# STM32F4_TFT-Proto_Adapter.net
KiCad netlist of a schematic drawn in EAGLE
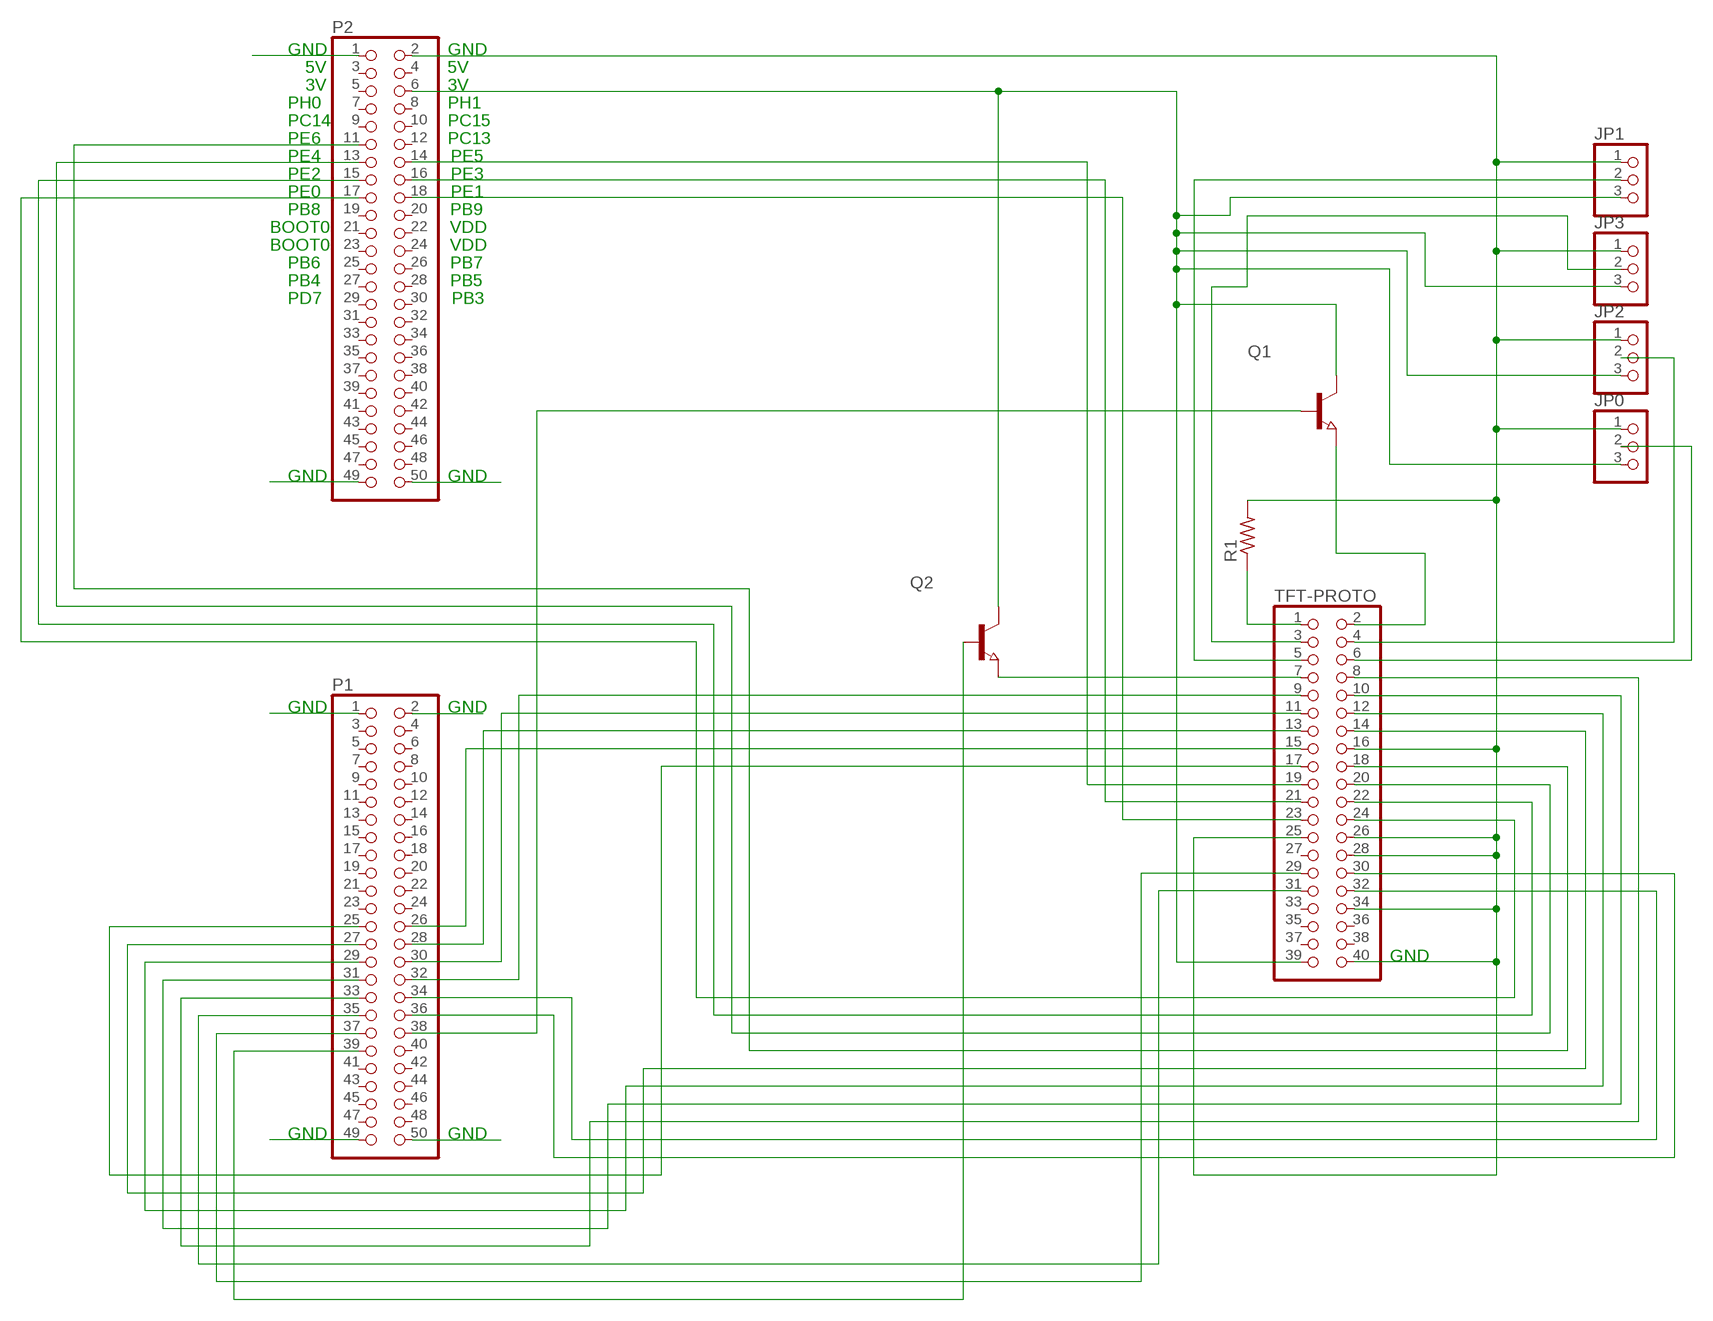
[diagram p0: schematic, sheet 1]

(export (version "E")
  (design (tool "Eeschema 10.0.6"))
  (components
    (comp (ref "JP0")
      (value "PINHD-1X3")
      (footprint "eagle-import:1X03")
      (libsource (lib "eagle-import") (part "PINHD-1X3"))
    )
    (comp (ref "JP1")
      (value "PINHD-1X3")
      (footprint "eagle-import:1X03")
      (libsource (lib "eagle-import") (part "PINHD-1X3"))
    )
    (comp (ref "JP2")
      (value "PINHD-1X3")
      (footprint "eagle-import:1X03")
      (libsource (lib "eagle-import") (part "PINHD-1X3"))
    )
    (comp (ref "JP3")
      (value "PINHD-1X3")
      (footprint "eagle-import:1X03")
      (libsource (lib "eagle-import") (part "PINHD-1X3"))
    )
    (comp (ref "P1")
      (value "PINHD-2X25")
      (footprint "eagle-import:2X25")
      (libsource (lib "eagle-import") (part "PINHD-2X25"))
    )
    (comp (ref "P2")
      (value "PINHD-2X25")
      (footprint "eagle-import:2X25")
      (libsource (lib "eagle-import") (part "PINHD-2X25"))
    )
    (comp (ref "Q1")
      (value "NPN-TRANSISTOR_SOT23")
      (footprint "eagle-import:SOT23")
      (libsource (lib "eagle-import") (part "NPN-TRANSISTOR_SOT23"))
    )
    (comp (ref "Q2")
      (value "NPN-TRANSISTOR_SOT23")
      (footprint "eagle-import:SOT23")
      (libsource (lib "eagle-import") (part "NPN-TRANSISTOR_SOT23"))
    )
    (comp (ref "R1")
      (value "R-US_R0805")
      (footprint "eagle-import:R0805")
      (libsource (lib "eagle-import") (part "R-US_R0805"))
    )
    (comp (ref "TFT-PROTO")
      (value "PINHD-2X20")
      (footprint "eagle-import:2X20")
      (libsource (lib "eagle-import") (part "PINHD-2X20"))
    )
  )
  (nets
    (net (code "1") (name "/GND") (class "Default")
      (node (ref "JP0") (pin "1") (pinfunction "1_1") (pintype "passive"))
      (node (ref "JP1") (pin "1") (pinfunction "1_1") (pintype "passive"))
      (node (ref "JP2") (pin "1") (pinfunction "1_1") (pintype "passive"))
      (node (ref "JP3") (pin "1") (pinfunction "1_1") (pintype "passive"))
      (node (ref "P1") (pin "1") (pinfunction "1_1") (pintype "passive"))
      (node (ref "P1") (pin "2") (pinfunction "2_2") (pintype "passive"))
      (node (ref "P1") (pin "49") (pinfunction "49_49") (pintype "passive"))
      (node (ref "P1") (pin "50") (pinfunction "50_50") (pintype "passive"))
      (node (ref "P2") (pin "1") (pinfunction "1_1") (pintype "passive"))
      (node (ref "P2") (pin "2") (pinfunction "2_2") (pintype "passive"))
      (node (ref "P2") (pin "49") (pinfunction "49_49") (pintype "passive"))
      (node (ref "P2") (pin "50") (pinfunction "50_50") (pintype "passive"))
      (node (ref "R1") (pin "2") (pinfunction "2_2") (pintype "passive"))
      (node (ref "TFT-PROTO") (pin "16") (pinfunction "16_16") (pintype "passive"))
      (node (ref "TFT-PROTO") (pin "25") (pinfunction "25_25") (pintype "passive"))
      (node (ref "TFT-PROTO") (pin "26") (pinfunction "26_26") (pintype "passive"))
      (node (ref "TFT-PROTO") (pin "28") (pinfunction "28_28") (pintype "passive"))
      (node (ref "TFT-PROTO") (pin "34") (pinfunction "34_34") (pintype "passive"))
      (node (ref "TFT-PROTO") (pin "40") (pinfunction "40_40") (pintype "passive"))
    )
    (net (code "2") (name "Net-(JP0-Pad2)") (class "Default")
      (node (ref "JP0") (pin "2") (pinfunction "2_2") (pintype "passive"))
      (node (ref "TFT-PROTO") (pin "6") (pinfunction "6_6") (pintype "passive"))
    )
    (net (code "3") (name "Net-(JP1-Pad2)") (class "Default")
      (node (ref "JP1") (pin "2") (pinfunction "2_2") (pintype "passive"))
      (node (ref "TFT-PROTO") (pin "5") (pinfunction "5_5") (pintype "passive"))
    )
    (net (code "4") (name "Net-(JP2-Pad2)") (class "Default")
      (node (ref "JP2") (pin "2") (pinfunction "2_2") (pintype "passive"))
      (node (ref "TFT-PROTO") (pin "4") (pinfunction "4_4") (pintype "passive"))
    )
    (net (code "5") (name "Net-(JP3-Pad2)") (class "Default")
      (node (ref "JP3") (pin "2") (pinfunction "2_2") (pintype "passive"))
      (node (ref "TFT-PROTO") (pin "3") (pinfunction "3_3") (pintype "passive"))
    )
    (net (code "6") (name "Net-(P1-Pad25)") (class "Default")
      (node (ref "P1") (pin "25") (pinfunction "25_25") (pintype "passive"))
      (node (ref "TFT-PROTO") (pin "17") (pinfunction "17_17") (pintype "passive"))
    )
    (net (code "7") (name "Net-(P1-Pad26)") (class "Default")
      (node (ref "P1") (pin "26") (pinfunction "26_26") (pintype "passive"))
      (node (ref "TFT-PROTO") (pin "15") (pinfunction "15_15") (pintype "passive"))
    )
    (net (code "8") (name "Net-(P1-Pad27)") (class "Default")
      (node (ref "P1") (pin "27") (pinfunction "27_27") (pintype "passive"))
      (node (ref "TFT-PROTO") (pin "14") (pinfunction "14_14") (pintype "passive"))
    )
    (net (code "9") (name "Net-(P1-Pad28)") (class "Default")
      (node (ref "P1") (pin "28") (pinfunction "28_28") (pintype "passive"))
      (node (ref "TFT-PROTO") (pin "13") (pinfunction "13_13") (pintype "passive"))
    )
    (net (code "10") (name "Net-(P1-Pad29)") (class "Default")
      (node (ref "P1") (pin "29") (pinfunction "29_29") (pintype "passive"))
      (node (ref "TFT-PROTO") (pin "12") (pinfunction "12_12") (pintype "passive"))
    )
    (net (code "11") (name "Net-(P1-Pad30)") (class "Default")
      (node (ref "P1") (pin "30") (pinfunction "30_30") (pintype "passive"))
      (node (ref "TFT-PROTO") (pin "11") (pinfunction "11_11") (pintype "passive"))
    )
    (net (code "12") (name "Net-(P1-Pad31)") (class "Default")
      (node (ref "P1") (pin "31") (pinfunction "31_31") (pintype "passive"))
      (node (ref "TFT-PROTO") (pin "10") (pinfunction "10_10") (pintype "passive"))
    )
    (net (code "13") (name "Net-(P1-Pad32)") (class "Default")
      (node (ref "P1") (pin "32") (pinfunction "32_32") (pintype "passive"))
      (node (ref "TFT-PROTO") (pin "9") (pinfunction "9_9") (pintype "passive"))
    )
    (net (code "14") (name "Net-(P1-Pad33)") (class "Default")
      (node (ref "P1") (pin "33") (pinfunction "33_33") (pintype "passive"))
      (node (ref "TFT-PROTO") (pin "8") (pinfunction "8_8") (pintype "passive"))
    )
    (net (code "15") (name "Net-(P1-Pad34)") (class "Default")
      (node (ref "P1") (pin "34") (pinfunction "34_34") (pintype "passive"))
      (node (ref "TFT-PROTO") (pin "32") (pinfunction "32_32") (pintype "passive"))
    )
    (net (code "16") (name "Net-(P1-Pad35)") (class "Default")
      (node (ref "P1") (pin "35") (pinfunction "35_35") (pintype "passive"))
      (node (ref "TFT-PROTO") (pin "31") (pinfunction "31_31") (pintype "passive"))
    )
    (net (code "17") (name "Net-(P1-Pad36)") (class "Default")
      (node (ref "P1") (pin "36") (pinfunction "36_36") (pintype "passive"))
      (node (ref "TFT-PROTO") (pin "30") (pinfunction "30_30") (pintype "passive"))
    )
    (net (code "18") (name "Net-(P1-Pad37)") (class "Default")
      (node (ref "P1") (pin "37") (pinfunction "37_37") (pintype "passive"))
      (node (ref "TFT-PROTO") (pin "29") (pinfunction "29_29") (pintype "passive"))
    )
    (net (code "19") (name "Net-(P2-Pad11)") (class "Default")
      (node (ref "P2") (pin "11") (pinfunction "11_11") (pintype "passive"))
      (node (ref "TFT-PROTO") (pin "18") (pinfunction "18_18") (pintype "passive"))
    )
    (net (code "20") (name "Net-(P2-Pad13)") (class "Default")
      (node (ref "P2") (pin "13") (pinfunction "13_13") (pintype "passive"))
      (node (ref "TFT-PROTO") (pin "20") (pinfunction "20_20") (pintype "passive"))
    )
    (net (code "21") (name "Net-(P2-Pad14)") (class "Default")
      (node (ref "P2") (pin "14") (pinfunction "14_14") (pintype "passive"))
      (node (ref "TFT-PROTO") (pin "19") (pinfunction "19_19") (pintype "passive"))
    )
    (net (code "22") (name "Net-(P2-Pad15)") (class "Default")
      (node (ref "P2") (pin "15") (pinfunction "15_15") (pintype "passive"))
      (node (ref "TFT-PROTO") (pin "22") (pinfunction "22_22") (pintype "passive"))
    )
    (net (code "23") (name "Net-(P2-Pad16)") (class "Default")
      (node (ref "P2") (pin "16") (pinfunction "16_16") (pintype "passive"))
      (node (ref "TFT-PROTO") (pin "21") (pinfunction "21_21") (pintype "passive"))
    )
    (net (code "24") (name "Net-(P2-Pad17)") (class "Default")
      (node (ref "P2") (pin "17") (pinfunction "17_17") (pintype "passive"))
      (node (ref "TFT-PROTO") (pin "24") (pinfunction "24_24") (pintype "passive"))
    )
    (net (code "25") (name "Net-(P2-Pad18)") (class "Default")
      (node (ref "P2") (pin "18") (pinfunction "18_18") (pintype "passive"))
      (node (ref "TFT-PROTO") (pin "23") (pinfunction "23_23") (pintype "passive"))
    )
    (net (code "26") (name "Net-(Q1-B)") (class "Default")
      (node (ref "P1") (pin "38") (pinfunction "38_38") (pintype "passive"))
      (node (ref "Q1") (pin "1") (pinfunction "B_1") (pintype "passive"))
    )
    (net (code "27") (name "Net-(Q1-C)") (class "Default")
      (node (ref "JP0") (pin "3") (pinfunction "3_3") (pintype "passive"))
      (node (ref "JP1") (pin "3") (pinfunction "3_3") (pintype "passive"))
      (node (ref "JP2") (pin "3") (pinfunction "3_3") (pintype "passive"))
      (node (ref "JP3") (pin "3") (pinfunction "3_3") (pintype "passive"))
      (node (ref "P2") (pin "6") (pinfunction "6_6") (pintype "passive"))
      (node (ref "Q1") (pin "3") (pinfunction "C_3") (pintype "passive"))
      (node (ref "Q2") (pin "3") (pinfunction "C_3") (pintype "passive"))
      (node (ref "TFT-PROTO") (pin "39") (pinfunction "39_39") (pintype "passive"))
    )
    (net (code "28") (name "Net-(Q1-E)") (class "Default")
      (node (ref "Q1") (pin "2") (pinfunction "E_2") (pintype "passive"))
      (node (ref "TFT-PROTO") (pin "2") (pinfunction "2_2") (pintype "passive"))
    )
    (net (code "29") (name "Net-(Q2-B)") (class "Default")
      (node (ref "P1") (pin "39") (pinfunction "39_39") (pintype "passive"))
      (node (ref "Q2") (pin "1") (pinfunction "B_1") (pintype "passive"))
    )
    (net (code "30") (name "Net-(Q2-E)") (class "Default")
      (node (ref "Q2") (pin "2") (pinfunction "E_2") (pintype "passive"))
      (node (ref "TFT-PROTO") (pin "7") (pinfunction "7_7") (pintype "passive"))
    )
    (net (code "31") (name "Net-(R1-Pad1)") (class "Default")
      (node (ref "R1") (pin "1") (pinfunction "1_1") (pintype "passive"))
      (node (ref "TFT-PROTO") (pin "1") (pinfunction "1_1") (pintype "passive"))
    )
    (net (code "32") (name "unconnected-(P1-Pad3)") (class "Default")
      (node (ref "P1") (pin "3") (pinfunction "3_3") (pintype "passive"))
    )
    (net (code "33") (name "unconnected-(P1-Pad4)") (class "Default")
      (node (ref "P1") (pin "4") (pinfunction "4_4") (pintype "passive"))
    )
    (net (code "34") (name "unconnected-(P1-Pad5)") (class "Default")
      (node (ref "P1") (pin "5") (pinfunction "5_5") (pintype "passive"))
    )
    (net (code "35") (name "unconnected-(P1-Pad6)") (class "Default")
      (node (ref "P1") (pin "6") (pinfunction "6_6") (pintype "passive"))
    )
    (net (code "36") (name "unconnected-(P1-Pad7)") (class "Default")
      (node (ref "P1") (pin "7") (pinfunction "7_7") (pintype "passive"))
    )
    (net (code "37") (name "unconnected-(P1-Pad8)") (class "Default")
      (node (ref "P1") (pin "8") (pinfunction "8_8") (pintype "passive"))
    )
    (net (code "38") (name "unconnected-(P1-Pad9)") (class "Default")
      (node (ref "P1") (pin "9") (pinfunction "9_9") (pintype "passive"))
    )
    (net (code "39") (name "unconnected-(P1-Pad10)") (class "Default")
      (node (ref "P1") (pin "10") (pinfunction "10_10") (pintype "passive"))
    )
    (net (code "40") (name "unconnected-(P1-Pad11)") (class "Default")
      (node (ref "P1") (pin "11") (pinfunction "11_11") (pintype "passive"))
    )
    (net (code "41") (name "unconnected-(P1-Pad12)") (class "Default")
      (node (ref "P1") (pin "12") (pinfunction "12_12") (pintype "passive"))
    )
    (net (code "42") (name "unconnected-(P1-Pad13)") (class "Default")
      (node (ref "P1") (pin "13") (pinfunction "13_13") (pintype "passive"))
    )
    (net (code "43") (name "unconnected-(P1-Pad14)") (class "Default")
      (node (ref "P1") (pin "14") (pinfunction "14_14") (pintype "passive"))
    )
    (net (code "44") (name "unconnected-(P1-Pad15)") (class "Default")
      (node (ref "P1") (pin "15") (pinfunction "15_15") (pintype "passive"))
    )
    (net (code "45") (name "unconnected-(P1-Pad16)") (class "Default")
      (node (ref "P1") (pin "16") (pinfunction "16_16") (pintype "passive"))
    )
    (net (code "46") (name "unconnected-(P1-Pad17)") (class "Default")
      (node (ref "P1") (pin "17") (pinfunction "17_17") (pintype "passive"))
    )
    (net (code "47") (name "unconnected-(P1-Pad18)") (class "Default")
      (node (ref "P1") (pin "18") (pinfunction "18_18") (pintype "passive"))
    )
    (net (code "48") (name "unconnected-(P1-Pad19)") (class "Default")
      (node (ref "P1") (pin "19") (pinfunction "19_19") (pintype "passive"))
    )
    (net (code "49") (name "unconnected-(P1-Pad20)") (class "Default")
      (node (ref "P1") (pin "20") (pinfunction "20_20") (pintype "passive"))
    )
    (net (code "50") (name "unconnected-(P1-Pad21)") (class "Default")
      (node (ref "P1") (pin "21") (pinfunction "21_21") (pintype "passive"))
    )
    (net (code "51") (name "unconnected-(P1-Pad22)") (class "Default")
      (node (ref "P1") (pin "22") (pinfunction "22_22") (pintype "passive"))
    )
    (net (code "52") (name "unconnected-(P1-Pad23)") (class "Default")
      (node (ref "P1") (pin "23") (pinfunction "23_23") (pintype "passive"))
    )
    (net (code "53") (name "unconnected-(P1-Pad24)") (class "Default")
      (node (ref "P1") (pin "24") (pinfunction "24_24") (pintype "passive"))
    )
    (net (code "54") (name "unconnected-(P1-Pad40)") (class "Default")
      (node (ref "P1") (pin "40") (pinfunction "40_40") (pintype "passive"))
    )
    (net (code "55") (name "unconnected-(P1-Pad41)") (class "Default")
      (node (ref "P1") (pin "41") (pinfunction "41_41") (pintype "passive"))
    )
    (net (code "56") (name "unconnected-(P1-Pad42)") (class "Default")
      (node (ref "P1") (pin "42") (pinfunction "42_42") (pintype "passive"))
    )
    (net (code "57") (name "unconnected-(P1-Pad43)") (class "Default")
      (node (ref "P1") (pin "43") (pinfunction "43_43") (pintype "passive"))
    )
    (net (code "58") (name "unconnected-(P1-Pad44)") (class "Default")
      (node (ref "P1") (pin "44") (pinfunction "44_44") (pintype "passive"))
    )
    (net (code "59") (name "unconnected-(P1-Pad45)") (class "Default")
      (node (ref "P1") (pin "45") (pinfunction "45_45") (pintype "passive"))
    )
    (net (code "60") (name "unconnected-(P1-Pad46)") (class "Default")
      (node (ref "P1") (pin "46") (pinfunction "46_46") (pintype "passive"))
    )
    (net (code "61") (name "unconnected-(P1-Pad47)") (class "Default")
      (node (ref "P1") (pin "47") (pinfunction "47_47") (pintype "passive"))
    )
    (net (code "62") (name "unconnected-(P1-Pad48)") (class "Default")
      (node (ref "P1") (pin "48") (pinfunction "48_48") (pintype "passive"))
    )
    (net (code "63") (name "unconnected-(P2-Pad3)") (class "Default")
      (node (ref "P2") (pin "3") (pinfunction "3_3") (pintype "passive"))
    )
    (net (code "64") (name "unconnected-(P2-Pad4)") (class "Default")
      (node (ref "P2") (pin "4") (pinfunction "4_4") (pintype "passive"))
    )
    (net (code "65") (name "unconnected-(P2-Pad5)") (class "Default")
      (node (ref "P2") (pin "5") (pinfunction "5_5") (pintype "passive"))
    )
    (net (code "66") (name "unconnected-(P2-Pad7)") (class "Default")
      (node (ref "P2") (pin "7") (pinfunction "7_7") (pintype "passive"))
    )
    (net (code "67") (name "unconnected-(P2-Pad8)") (class "Default")
      (node (ref "P2") (pin "8") (pinfunction "8_8") (pintype "passive"))
    )
    (net (code "68") (name "unconnected-(P2-Pad9)") (class "Default")
      (node (ref "P2") (pin "9") (pinfunction "9_9") (pintype "passive"))
    )
    (net (code "69") (name "unconnected-(P2-Pad10)") (class "Default")
      (node (ref "P2") (pin "10") (pinfunction "10_10") (pintype "passive"))
    )
    (net (code "70") (name "unconnected-(P2-Pad12)") (class "Default")
      (node (ref "P2") (pin "12") (pinfunction "12_12") (pintype "passive"))
    )
    (net (code "71") (name "unconnected-(P2-Pad19)") (class "Default")
      (node (ref "P2") (pin "19") (pinfunction "19_19") (pintype "passive"))
    )
    (net (code "72") (name "unconnected-(P2-Pad20)") (class "Default")
      (node (ref "P2") (pin "20") (pinfunction "20_20") (pintype "passive"))
    )
    (net (code "73") (name "unconnected-(P2-Pad21)") (class "Default")
      (node (ref "P2") (pin "21") (pinfunction "21_21") (pintype "passive"))
    )
    (net (code "74") (name "unconnected-(P2-Pad22)") (class "Default")
      (node (ref "P2") (pin "22") (pinfunction "22_22") (pintype "passive"))
    )
    (net (code "75") (name "unconnected-(P2-Pad23)") (class "Default")
      (node (ref "P2") (pin "23") (pinfunction "23_23") (pintype "passive"))
    )
    (net (code "76") (name "unconnected-(P2-Pad24)") (class "Default")
      (node (ref "P2") (pin "24") (pinfunction "24_24") (pintype "passive"))
    )
    (net (code "77") (name "unconnected-(P2-Pad25)") (class "Default")
      (node (ref "P2") (pin "25") (pinfunction "25_25") (pintype "passive"))
    )
    (net (code "78") (name "unconnected-(P2-Pad26)") (class "Default")
      (node (ref "P2") (pin "26") (pinfunction "26_26") (pintype "passive"))
    )
    (net (code "79") (name "unconnected-(P2-Pad27)") (class "Default")
      (node (ref "P2") (pin "27") (pinfunction "27_27") (pintype "passive"))
    )
    (net (code "80") (name "unconnected-(P2-Pad28)") (class "Default")
      (node (ref "P2") (pin "28") (pinfunction "28_28") (pintype "passive"))
    )
    (net (code "81") (name "unconnected-(P2-Pad29)") (class "Default")
      (node (ref "P2") (pin "29") (pinfunction "29_29") (pintype "passive"))
    )
    (net (code "82") (name "unconnected-(P2-Pad30)") (class "Default")
      (node (ref "P2") (pin "30") (pinfunction "30_30") (pintype "passive"))
    )
    (net (code "83") (name "unconnected-(P2-Pad31)") (class "Default")
      (node (ref "P2") (pin "31") (pinfunction "31_31") (pintype "passive"))
    )
    (net (code "84") (name "unconnected-(P2-Pad32)") (class "Default")
      (node (ref "P2") (pin "32") (pinfunction "32_32") (pintype "passive"))
    )
    (net (code "85") (name "unconnected-(P2-Pad33)") (class "Default")
      (node (ref "P2") (pin "33") (pinfunction "33_33") (pintype "passive"))
    )
    (net (code "86") (name "unconnected-(P2-Pad34)") (class "Default")
      (node (ref "P2") (pin "34") (pinfunction "34_34") (pintype "passive"))
    )
    (net (code "87") (name "unconnected-(P2-Pad35)") (class "Default")
      (node (ref "P2") (pin "35") (pinfunction "35_35") (pintype "passive"))
    )
    (net (code "88") (name "unconnected-(P2-Pad36)") (class "Default")
      (node (ref "P2") (pin "36") (pinfunction "36_36") (pintype "passive"))
    )
    (net (code "89") (name "unconnected-(P2-Pad37)") (class "Default")
      (node (ref "P2") (pin "37") (pinfunction "37_37") (pintype "passive"))
    )
    (net (code "90") (name "unconnected-(P2-Pad38)") (class "Default")
      (node (ref "P2") (pin "38") (pinfunction "38_38") (pintype "passive"))
    )
    (net (code "91") (name "unconnected-(P2-Pad39)") (class "Default")
      (node (ref "P2") (pin "39") (pinfunction "39_39") (pintype "passive"))
    )
    (net (code "92") (name "unconnected-(P2-Pad40)") (class "Default")
      (node (ref "P2") (pin "40") (pinfunction "40_40") (pintype "passive"))
    )
    (net (code "93") (name "unconnected-(P2-Pad41)") (class "Default")
      (node (ref "P2") (pin "41") (pinfunction "41_41") (pintype "passive"))
    )
    (net (code "94") (name "unconnected-(P2-Pad42)") (class "Default")
      (node (ref "P2") (pin "42") (pinfunction "42_42") (pintype "passive"))
    )
    (net (code "95") (name "unconnected-(P2-Pad43)") (class "Default")
      (node (ref "P2") (pin "43") (pinfunction "43_43") (pintype "passive"))
    )
    (net (code "96") (name "unconnected-(P2-Pad44)") (class "Default")
      (node (ref "P2") (pin "44") (pinfunction "44_44") (pintype "passive"))
    )
    (net (code "97") (name "unconnected-(P2-Pad45)") (class "Default")
      (node (ref "P2") (pin "45") (pinfunction "45_45") (pintype "passive"))
    )
    (net (code "98") (name "unconnected-(P2-Pad46)") (class "Default")
      (node (ref "P2") (pin "46") (pinfunction "46_46") (pintype "passive"))
    )
    (net (code "99") (name "unconnected-(P2-Pad47)") (class "Default")
      (node (ref "P2") (pin "47") (pinfunction "47_47") (pintype "passive"))
    )
    (net (code "100") (name "unconnected-(P2-Pad48)") (class "Default")
      (node (ref "P2") (pin "48") (pinfunction "48_48") (pintype "passive"))
    )
    (net (code "101") (name "unconnected-(TFT-PROTO-Pad27)") (class "Default")
      (node (ref "TFT-PROTO") (pin "27") (pinfunction "27_27") (pintype "passive"))
    )
    (net (code "102") (name "unconnected-(TFT-PROTO-Pad33)") (class "Default")
      (node (ref "TFT-PROTO") (pin "33") (pinfunction "33_33") (pintype "passive"))
    )
    (net (code "103") (name "unconnected-(TFT-PROTO-Pad35)") (class "Default")
      (node (ref "TFT-PROTO") (pin "35") (pinfunction "35_35") (pintype "passive"))
    )
    (net (code "104") (name "unconnected-(TFT-PROTO-Pad36)") (class "Default")
      (node (ref "TFT-PROTO") (pin "36") (pinfunction "36_36") (pintype "passive"))
    )
    (net (code "105") (name "unconnected-(TFT-PROTO-Pad37)") (class "Default")
      (node (ref "TFT-PROTO") (pin "37") (pinfunction "37_37") (pintype "passive"))
    )
    (net (code "106") (name "unconnected-(TFT-PROTO-Pad38)") (class "Default")
      (node (ref "TFT-PROTO") (pin "38") (pinfunction "38_38") (pintype "passive"))
    )
  )
)
